# STM32_MPU_IOs.net
KiCad netlist of a schematic drawn in Altium Designer
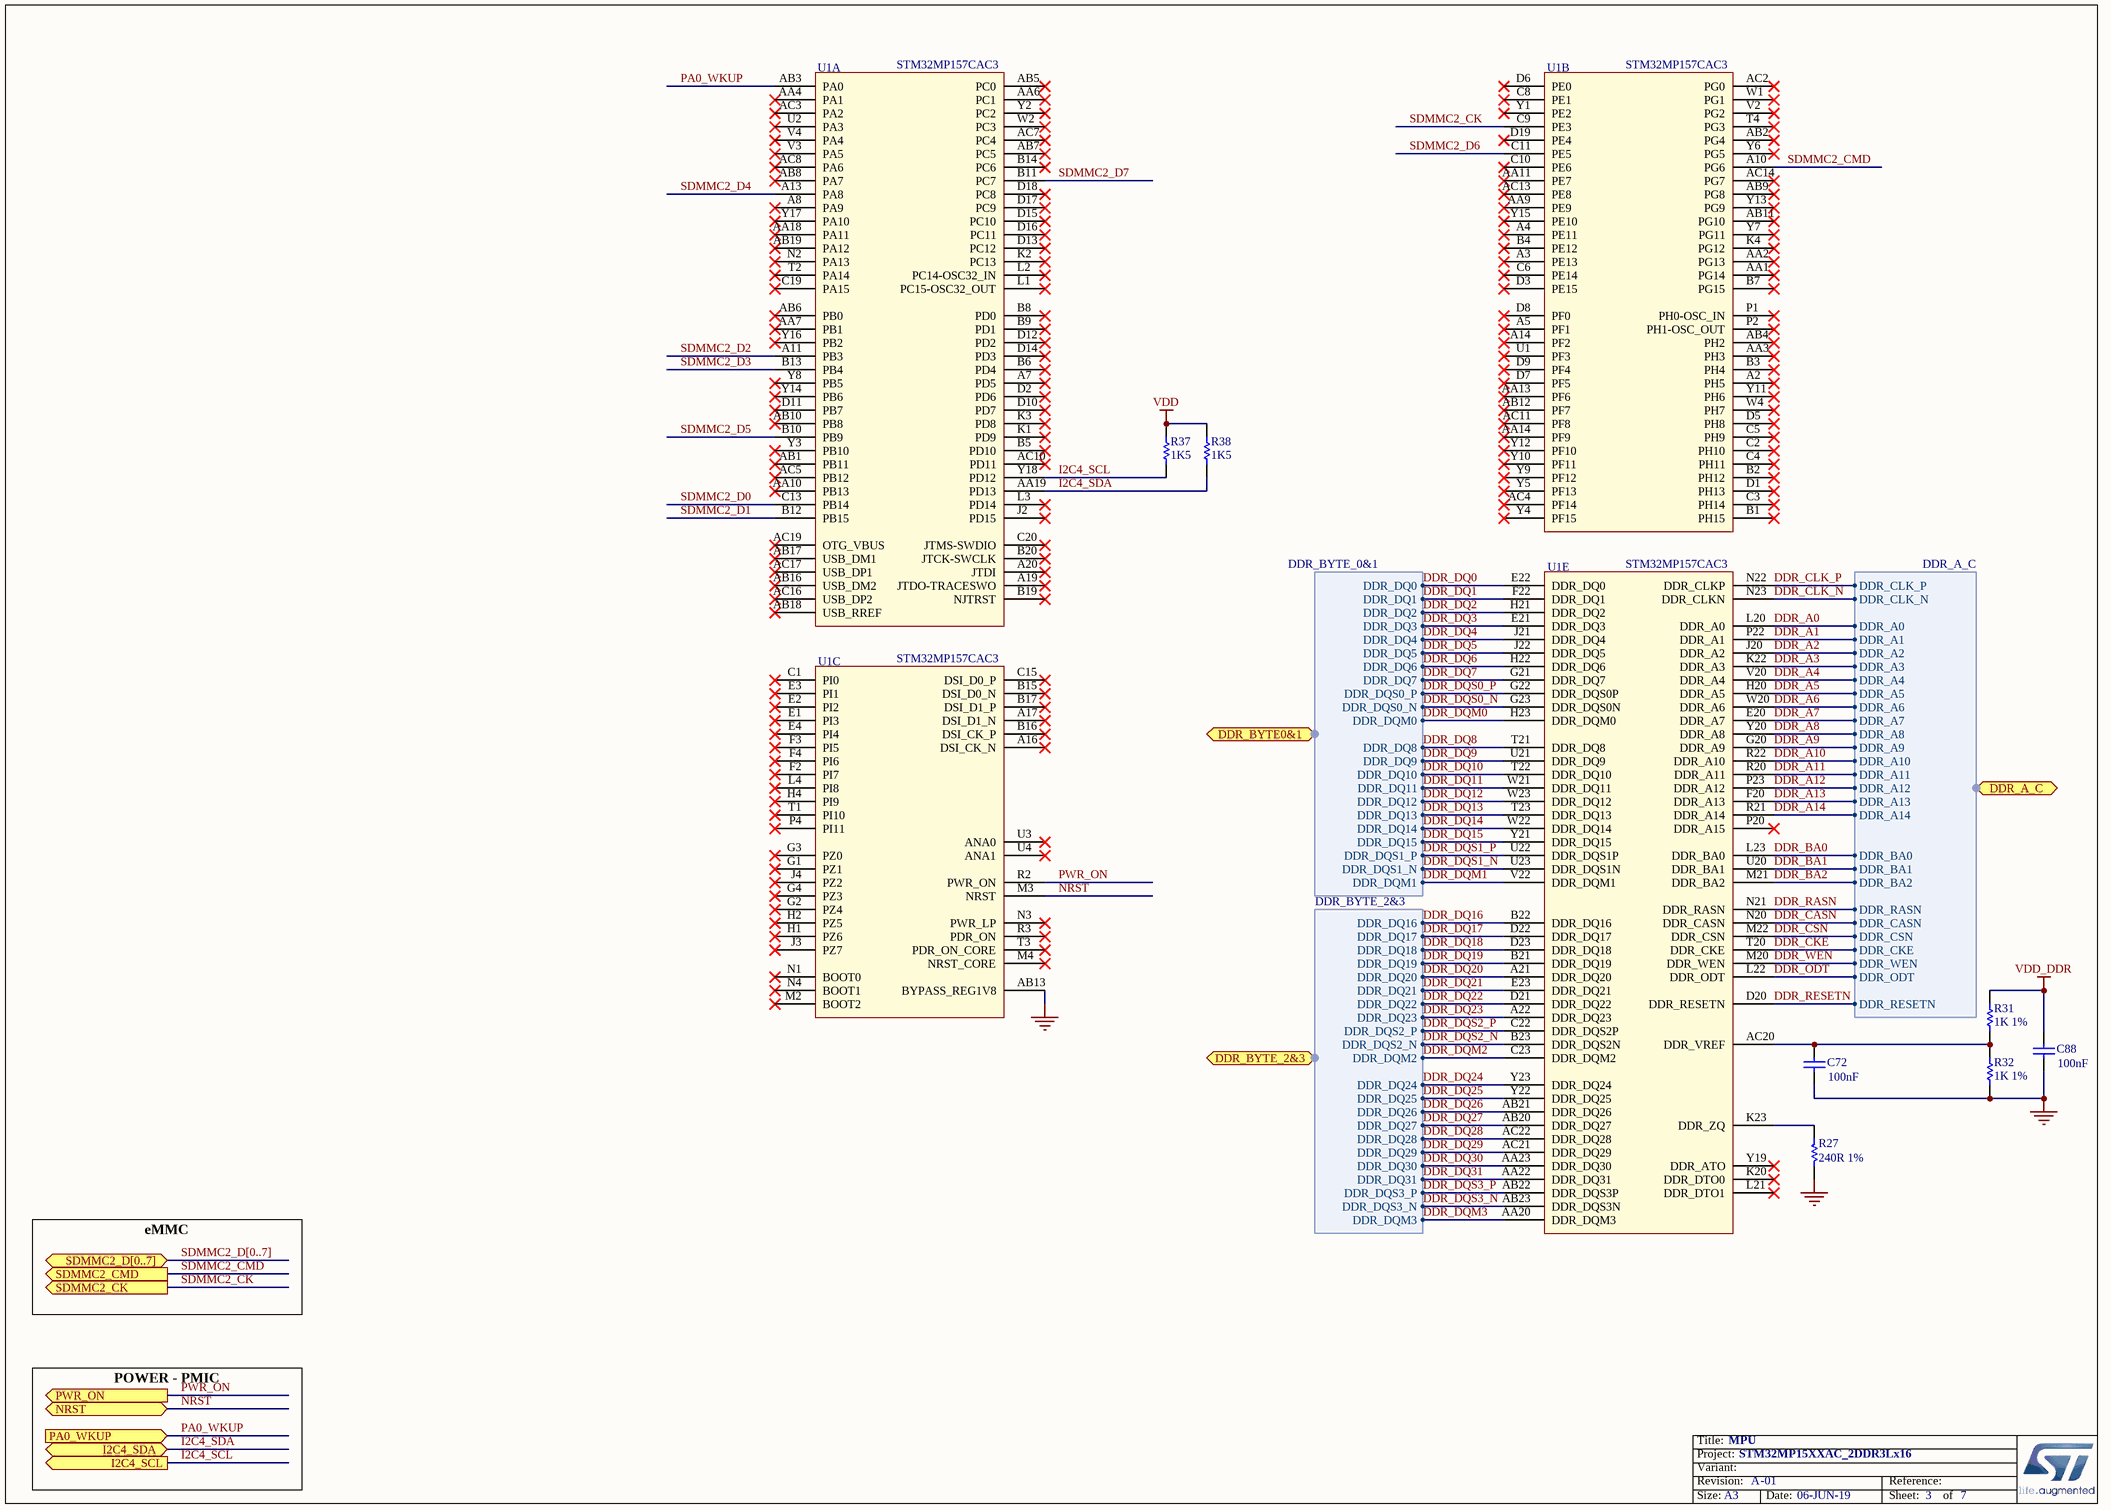
[diagram p0: STM32_MPU_IOs.SchDoc]

(export (version "E")
  (design (tool "Eeschema 10.0.6"))
  (components
    (comp (ref "C72")
      (value "100nF")
      (footprint "C0402")
      (description "Capacitor,100nF,16V,X7R,10%,0402")
      (fields
        (field (name "INTERNAL_PART_NUMBER") "MCD-00006")
        (field (name "MANUFACTURER_PART_NUMBER") "CC0402KRX7R7BB104")
        (field (name "PROVIDED_BY") "Subcon")
      )
      (libsource (lib "MCD_PARTS_database") (part "Capacitor"))
    )
    (comp (ref "C88")
      (value "100nF")
      (footprint "C0402")
      (description "Capacitor,100nF,16V,X7R,10%,0402")
      (fields
        (field (name "INTERNAL_PART_NUMBER") "MCD-00006")
        (field (name "MANUFACTURER_PART_NUMBER") "CC0402KRX7R7BB104")
        (field (name "PROVIDED_BY") "Subcon")
      )
      (libsource (lib "MCD_PARTS_database") (part "Capacitor"))
    )
    (comp (ref "R27")
      (value "240R 1%")
      (footprint "R0402")
      (description "Resistor,240R,0402,1%,1/16W")
      (fields
        (field (name "INTERNAL_PART_NUMBER") "MCD-00120")
        (field (name "MANUFACTURER_PART_NUMBER") "RC0402FR-07240RL")
        (field (name "PROVIDED_BY") "Subcon")
      )
      (libsource (lib "MCD_PARTS_database") (part "Resistor"))
    )
    (comp (ref "R31")
      (value "1K 1%")
      (footprint "R0402")
      (description "Resistor,1K,0402,1%,1/16W")
      (fields
        (field (name "INTERNAL_PART_NUMBER") "MCD-00061")
        (field (name "MANUFACTURER_PART_NUMBER") "RC0402FR-071KL")
        (field (name "PROVIDED_BY") "SUBCO")
      )
      (libsource (lib "MCD_PARTS_database") (part "Resistor"))
    )
    (comp (ref "R32")
      (value "1K 1%")
      (footprint "R0402")
      (description "Resistor,1K,0402,1%,1/16W")
      (fields
        (field (name "INTERNAL_PART_NUMBER") "MCD-00061")
        (field (name "MANUFACTURER_PART_NUMBER") "RC0402FR-071KL")
        (field (name "PROVIDED_BY") "SUBCO")
      )
      (libsource (lib "MCD_PARTS_database") (part "Resistor"))
    )
    (comp (ref "R37")
      (value "1K5")
      (footprint "R0402")
      (description "Resistor,1K5,0402,1%,1/16W")
      (fields
        (field (name "INTERNAL_PART_NUMBER") "MCD-00068")
        (field (name "MANUFACTURER_PART_NUMBER") "RC0402FR-071K5L")
        (field (name "PROVIDED_BY") "Subcon")
      )
      (libsource (lib "MCD_PARTS_database") (part "Resistor"))
    )
    (comp (ref "R38")
      (value "1K5")
      (footprint "R0402")
      (description "Resistor,1K5,0402,1%,1/16W")
      (fields
        (field (name "INTERNAL_PART_NUMBER") "MCD-00068")
        (field (name "MANUFACTURER_PART_NUMBER") "RC0402FR-071K5L")
        (field (name "PROVIDED_BY") "Subcon")
      )
      (libsource (lib "MCD_PARTS_database") (part "Resistor"))
    )
    (comp (ref "U1")
      (value "STM32MP157CAC3")
      (footprint "ICC_TFBGA361_12X12_STM32MP157CAC3_P050-065")
      (description "MPU TFBGA12x12 secure boot+crypto")
      (fields
        (field (name "INTERNAL_PART_NUMBER") "MCD-00677")
        (field (name "MANUFACTURER") "STMICROELECTRONICS")
        (field (name "PROVIDED_BY") "STM")
      )
      (libsource (lib "MCD_PARTS_database") (part "STM32MP157CAC3"))
    )
  )
  (nets
    (net (code "4") (name "/DDR_A0") (class "Default")
      (node (ref "U1") (pin "L20") (pinfunction "DDR_A0_L20") (pintype "passive"))
    )
    (net (code "5") (name "/DDR_A1") (class "Default")
      (node (ref "U1") (pin "P22") (pinfunction "DDR_A1_P22") (pintype "passive"))
    )
    (net (code "6") (name "/DDR_A2") (class "Default")
      (node (ref "U1") (pin "J20") (pinfunction "DDR_A2_J20") (pintype "passive"))
    )
    (net (code "7") (name "/DDR_A3") (class "Default")
      (node (ref "U1") (pin "K22") (pinfunction "DDR_A3_K22") (pintype "passive"))
    )
    (net (code "8") (name "/DDR_A4") (class "Default")
      (node (ref "U1") (pin "V20") (pinfunction "DDR_A4_V20") (pintype "passive"))
    )
    (net (code "9") (name "/DDR_A5") (class "Default")
      (node (ref "U1") (pin "H20") (pinfunction "DDR_A5_H20") (pintype "passive"))
    )
    (net (code "10") (name "/DDR_A6") (class "Default")
      (node (ref "U1") (pin "W20") (pinfunction "DDR_A6_W20") (pintype "passive"))
    )
    (net (code "11") (name "/DDR_A7") (class "Default")
      (node (ref "U1") (pin "E20") (pinfunction "DDR_A7_E20") (pintype "passive"))
    )
    (net (code "12") (name "/DDR_A8") (class "Default")
      (node (ref "U1") (pin "Y20") (pinfunction "DDR_A8_Y20") (pintype "passive"))
    )
    (net (code "13") (name "/DDR_A9") (class "Default")
      (node (ref "U1") (pin "G20") (pinfunction "DDR_A9_G20") (pintype "passive"))
    )
    (net (code "14") (name "/DDR_A10") (class "Default")
      (node (ref "U1") (pin "R22") (pinfunction "DDR_A10_R22") (pintype "passive"))
    )
    (net (code "15") (name "/DDR_A11") (class "Default")
      (node (ref "U1") (pin "R20") (pinfunction "DDR_A11_R20") (pintype "passive"))
    )
    (net (code "16") (name "/DDR_A12") (class "Default")
      (node (ref "U1") (pin "P23") (pinfunction "DDR_A12_P23") (pintype "passive"))
    )
    (net (code "17") (name "/DDR_A13") (class "Default")
      (node (ref "U1") (pin "F20") (pinfunction "DDR_A13_F20") (pintype "passive"))
    )
    (net (code "18") (name "/DDR_A14") (class "Default")
      (node (ref "U1") (pin "R21") (pinfunction "DDR_A14_R21") (pintype "passive"))
    )
    (net (code "19") (name "/DDR_BA0") (class "Default")
      (node (ref "U1") (pin "L23") (pinfunction "DDR_BA0_L23") (pintype "passive"))
    )
    (net (code "20") (name "/DDR_BA1") (class "Default")
      (node (ref "U1") (pin "U20") (pinfunction "DDR_BA1_U20") (pintype "passive"))
    )
    (net (code "21") (name "/DDR_BA2") (class "Default")
      (node (ref "U1") (pin "M21") (pinfunction "DDR_BA2_M21") (pintype "passive"))
    )
    (net (code "22") (name "/DDR_CASN") (class "Default")
      (node (ref "U1") (pin "N20") (pinfunction "DDR_CASN_N20") (pintype "passive"))
    )
    (net (code "23") (name "/DDR_CKE") (class "Default")
      (node (ref "U1") (pin "T20") (pinfunction "DDR_CKE_T20") (pintype "passive"))
    )
    (net (code "24") (name "/DDR_CLK_N") (class "Default")
      (node (ref "U1") (pin "N23") (pinfunction "DDR_CLKN_N23") (pintype "passive"))
    )
    (net (code "25") (name "/DDR_CLK_P") (class "Default")
      (node (ref "U1") (pin "N22") (pinfunction "DDR_CLKP_N22") (pintype "passive"))
    )
    (net (code "26") (name "/DDR_CSN") (class "Default")
      (node (ref "U1") (pin "M22") (pinfunction "DDR_CSN_M22") (pintype "passive"))
    )
    (net (code "27") (name "/DDR_DQ0") (class "Default")
      (node (ref "U1") (pin "E22") (pinfunction "DDR_DQ0_E22") (pintype "passive"))
    )
    (net (code "28") (name "/DDR_DQ1") (class "Default")
      (node (ref "U1") (pin "F22") (pinfunction "DDR_DQ1_F22") (pintype "passive"))
    )
    (net (code "29") (name "/DDR_DQ2") (class "Default")
      (node (ref "U1") (pin "H21") (pinfunction "DDR_DQ2_H21") (pintype "passive"))
    )
    (net (code "30") (name "/DDR_DQ3") (class "Default")
      (node (ref "U1") (pin "E21") (pinfunction "DDR_DQ3_E21") (pintype "passive"))
    )
    (net (code "31") (name "/DDR_DQ4") (class "Default")
      (node (ref "U1") (pin "J21") (pinfunction "DDR_DQ4_J21") (pintype "passive"))
    )
    (net (code "32") (name "/DDR_DQ5") (class "Default")
      (node (ref "U1") (pin "J22") (pinfunction "DDR_DQ5_J22") (pintype "passive"))
    )
    (net (code "33") (name "/DDR_DQ6") (class "Default")
      (node (ref "U1") (pin "H22") (pinfunction "DDR_DQ6_H22") (pintype "passive"))
    )
    (net (code "34") (name "/DDR_DQ7") (class "Default")
      (node (ref "U1") (pin "G21") (pinfunction "DDR_DQ7_G21") (pintype "passive"))
    )
    (net (code "35") (name "/DDR_DQ8") (class "Default")
      (node (ref "U1") (pin "T21") (pinfunction "DDR_DQ8_T21") (pintype "passive"))
    )
    (net (code "36") (name "/DDR_DQ9") (class "Default")
      (node (ref "U1") (pin "U21") (pinfunction "DDR_DQ9_U21") (pintype "passive"))
    )
    (net (code "37") (name "/DDR_DQ10") (class "Default")
      (node (ref "U1") (pin "T22") (pinfunction "DDR_DQ10_T22") (pintype "passive"))
    )
    (net (code "38") (name "/DDR_DQ11") (class "Default")
      (node (ref "U1") (pin "W21") (pinfunction "DDR_DQ11_W21") (pintype "passive"))
    )
    (net (code "39") (name "/DDR_DQ12") (class "Default")
      (node (ref "U1") (pin "W23") (pinfunction "DDR_DQ12_W23") (pintype "passive"))
    )
    (net (code "40") (name "/DDR_DQ13") (class "Default")
      (node (ref "U1") (pin "T23") (pinfunction "DDR_DQ13_T23") (pintype "passive"))
    )
    (net (code "41") (name "/DDR_DQ14") (class "Default")
      (node (ref "U1") (pin "W22") (pinfunction "DDR_DQ14_W22") (pintype "passive"))
    )
    (net (code "42") (name "/DDR_DQ15") (class "Default")
      (node (ref "U1") (pin "Y21") (pinfunction "DDR_DQ15_Y21") (pintype "passive"))
    )
    (net (code "43") (name "/DDR_DQ16") (class "Default")
      (node (ref "U1") (pin "B22") (pinfunction "DDR_DQ16_B22") (pintype "passive"))
    )
    (net (code "44") (name "/DDR_DQ17") (class "Default")
      (node (ref "U1") (pin "D22") (pinfunction "DDR_DQ17_D22") (pintype "passive"))
    )
    (net (code "45") (name "/DDR_DQ18") (class "Default")
      (node (ref "U1") (pin "D23") (pinfunction "DDR_DQ18_D23") (pintype "passive"))
    )
    (net (code "46") (name "/DDR_DQ19") (class "Default")
      (node (ref "U1") (pin "B21") (pinfunction "DDR_DQ19_B21") (pintype "passive"))
    )
    (net (code "47") (name "/DDR_DQ20") (class "Default")
      (node (ref "U1") (pin "A21") (pinfunction "DDR_DQ20_A21") (pintype "passive"))
    )
    (net (code "48") (name "/DDR_DQ21") (class "Default")
      (node (ref "U1") (pin "E23") (pinfunction "DDR_DQ21_E23") (pintype "passive"))
    )
    (net (code "49") (name "/DDR_DQ22") (class "Default")
      (node (ref "U1") (pin "D21") (pinfunction "DDR_DQ22_D21") (pintype "passive"))
    )
    (net (code "50") (name "/DDR_DQ23") (class "Default")
      (node (ref "U1") (pin "A22") (pinfunction "DDR_DQ23_A22") (pintype "passive"))
    )
    (net (code "51") (name "/DDR_DQ24") (class "Default")
      (node (ref "U1") (pin "Y23") (pinfunction "DDR_DQ24_Y23") (pintype "passive"))
    )
    (net (code "52") (name "/DDR_DQ25") (class "Default")
      (node (ref "U1") (pin "Y22") (pinfunction "DDR_DQ25_Y22") (pintype "passive"))
    )
    (net (code "53") (name "/DDR_DQ26") (class "Default")
      (node (ref "U1") (pin "AB21") (pinfunction "DDR_DQ26_AB21") (pintype "passive"))
    )
    (net (code "54") (name "/DDR_DQ27") (class "Default")
      (node (ref "U1") (pin "AB20") (pinfunction "DDR_DQ27_AB20") (pintype "passive"))
    )
    (net (code "55") (name "/DDR_DQ28") (class "Default")
      (node (ref "U1") (pin "AC22") (pinfunction "DDR_DQ28_AC22") (pintype "passive"))
    )
    (net (code "56") (name "/DDR_DQ29") (class "Default")
      (node (ref "U1") (pin "AC21") (pinfunction "DDR_DQ29_AC21") (pintype "passive"))
    )
    (net (code "57") (name "/DDR_DQ30") (class "Default")
      (node (ref "U1") (pin "AA23") (pinfunction "DDR_DQ30_AA23") (pintype "passive"))
    )
    (net (code "58") (name "/DDR_DQ31") (class "Default")
      (node (ref "U1") (pin "AA22") (pinfunction "DDR_DQ31_AA22") (pintype "passive"))
    )
    (net (code "59") (name "/DDR_DQM0") (class "Default")
      (node (ref "U1") (pin "H23") (pinfunction "DDR_DQM0_H23") (pintype "passive"))
    )
    (net (code "60") (name "/DDR_DQM1") (class "Default")
      (node (ref "U1") (pin "V22") (pinfunction "DDR_DQM1_V22") (pintype "passive"))
    )
    (net (code "61") (name "/DDR_DQM2") (class "Default")
      (node (ref "U1") (pin "C23") (pinfunction "DDR_DQM2_C23") (pintype "passive"))
    )
    (net (code "62") (name "/DDR_DQM3") (class "Default")
      (node (ref "U1") (pin "AA20") (pinfunction "DDR_DQM3_AA20") (pintype "passive"))
    )
    (net (code "63") (name "/DDR_DQS0_N") (class "Default")
      (node (ref "U1") (pin "G23") (pinfunction "DDR_DQS0N_G23") (pintype "passive"))
    )
    (net (code "64") (name "/DDR_DQS0_P") (class "Default")
      (node (ref "U1") (pin "G22") (pinfunction "DDR_DQS0P_G22") (pintype "passive"))
    )
    (net (code "65") (name "/DDR_DQS1_N") (class "Default")
      (node (ref "U1") (pin "U23") (pinfunction "DDR_DQS1N_U23") (pintype "passive"))
    )
    (net (code "66") (name "/DDR_DQS1_P") (class "Default")
      (node (ref "U1") (pin "U22") (pinfunction "DDR_DQS1P_U22") (pintype "passive"))
    )
    (net (code "67") (name "/DDR_DQS2_N") (class "Default")
      (node (ref "U1") (pin "B23") (pinfunction "DDR_DQS2N_B23") (pintype "passive"))
    )
    (net (code "68") (name "/DDR_DQS2_P") (class "Default")
      (node (ref "U1") (pin "C22") (pinfunction "DDR_DQS2P_C22") (pintype "passive"))
    )
    (net (code "69") (name "/DDR_DQS3_N") (class "Default")
      (node (ref "U1") (pin "AB23") (pinfunction "DDR_DQS3N_AB23") (pintype "passive"))
    )
    (net (code "70") (name "/DDR_DQS3_P") (class "Default")
      (node (ref "U1") (pin "AB22") (pinfunction "DDR_DQS3P_AB22") (pintype "passive"))
    )
    (net (code "71") (name "/DDR_ODT") (class "Default")
      (node (ref "U1") (pin "L22") (pinfunction "DDR_ODT_L22") (pintype "passive"))
    )
    (net (code "72") (name "/DDR_RASN") (class "Default")
      (node (ref "U1") (pin "N21") (pinfunction "DDR_RASN_N21") (pintype "passive"))
    )
    (net (code "73") (name "/DDR_RESETN") (class "Default")
      (node (ref "U1") (pin "D20") (pinfunction "DDR_RESETN_D20") (pintype "passive"))
    )
    (net (code "74") (name "/DDR_WEN") (class "Default")
      (node (ref "U1") (pin "M20") (pinfunction "DDR_WEN_M20") (pintype "passive"))
    )
    (net (code "75") (name "/I2C4_SCL") (class "Default")
      (node (ref "R37") (pin "2") (pinfunction "2_2") (pintype "passive"))
      (node (ref "U1") (pin "Y18") (pinfunction "PD12_Y18") (pintype "passive"))
    )
    (net (code "76") (name "/I2C4_SDA") (class "Default")
      (node (ref "R38") (pin "2") (pinfunction "2_2") (pintype "passive"))
      (node (ref "U1") (pin "AA19") (pinfunction "PD13_AA19") (pintype "passive"))
    )
    (net (code "77") (name "/NRST") (class "Default")
      (node (ref "U1") (pin "M3") (pinfunction "NRST_M3") (pintype "passive"))
    )
    (net (code "78") (name "/PA0_WKUP") (class "Default")
      (node (ref "U1") (pin "AB3") (pinfunction "PA0_AB3") (pintype "passive"))
    )
    (net (code "79") (name "/PWR_ON") (class "Default")
      (node (ref "U1") (pin "R2") (pinfunction "PWR_ON_R2") (pintype "passive"))
    )
    (net (code "80") (name "/SDMMC2_CK") (class "Default")
      (node (ref "U1") (pin "C9") (pinfunction "PE3_C9") (pintype "passive"))
    )
    (net (code "81") (name "/SDMMC2_CMD") (class "Default")
      (node (ref "U1") (pin "A10") (pinfunction "PG6_A10") (pintype "passive"))
    )
    (net (code "82") (name "/SDMMC2_D0") (class "Default")
      (node (ref "U1") (pin "C13") (pinfunction "PB14_C13") (pintype "passive"))
    )
    (net (code "83") (name "/SDMMC2_D1") (class "Default")
      (node (ref "U1") (pin "B12") (pinfunction "PB15_B12") (pintype "passive"))
    )
    (net (code "84") (name "/SDMMC2_D2") (class "Default")
      (node (ref "U1") (pin "A11") (pinfunction "PB3_A11") (pintype "passive"))
    )
    (net (code "85") (name "/SDMMC2_D3") (class "Default")
      (node (ref "U1") (pin "B13") (pinfunction "PB4_B13") (pintype "passive"))
    )
    (net (code "86") (name "/SDMMC2_D4") (class "Default")
      (node (ref "U1") (pin "A13") (pinfunction "PA8_A13") (pintype "passive"))
    )
    (net (code "87") (name "/SDMMC2_D5") (class "Default")
      (node (ref "U1") (pin "B10") (pinfunction "PB9_B10") (pintype "passive"))
    )
    (net (code "88") (name "/SDMMC2_D6") (class "Default")
      (node (ref "U1") (pin "C11") (pinfunction "PE5_C11") (pintype "passive"))
    )
    (net (code "89") (name "/SDMMC2_D7") (class "Default")
      (node (ref "U1") (pin "B11") (pinfunction "PC7_B11") (pintype "passive"))
    )
    (net (code "94") (name "GND") (class "Default")
      (node (ref "C72") (pin "1") (pinfunction "1_1") (pintype "passive"))
      (node (ref "C88") (pin "1") (pinfunction "1_1") (pintype "passive"))
      (node (ref "R27") (pin "2") (pinfunction "2_2") (pintype "passive"))
      (node (ref "R32") (pin "1") (pinfunction "1_1") (pintype "passive"))
      (node (ref "U1") (pin "AB13") (pinfunction "BYPASS_REG1V8_AB13") (pintype "passive"))
    )
    (net (code "95") (name "Net-(U1E-DDR_VREF)") (class "Default")
      (node (ref "C72") (pin "2") (pinfunction "2_2") (pintype "passive"))
      (node (ref "R31") (pin "1") (pinfunction "1_1") (pintype "passive"))
      (node (ref "R32") (pin "2") (pinfunction "2_2") (pintype "passive"))
      (node (ref "U1") (pin "AC20") (pinfunction "DDR_VREF_AC20") (pintype "passive"))
    )
    (net (code "96") (name "Net-(U1E-DDR_ZQ)") (class "Default")
      (node (ref "R27") (pin "1") (pinfunction "1_1") (pintype "passive"))
      (node (ref "U1") (pin "K23") (pinfunction "DDR_ZQ_K23") (pintype "passive"))
    )
    (net (code "97") (name "VDD") (class "Default")
      (node (ref "R37") (pin "1") (pinfunction "1_1") (pintype "passive"))
      (node (ref "R38") (pin "1") (pinfunction "1_1") (pintype "passive"))
    )
    (net (code "98") (name "VDD_DDR") (class "Default")
      (node (ref "C88") (pin "2") (pinfunction "2_2") (pintype "passive"))
      (node (ref "R31") (pin "2") (pinfunction "2_2") (pintype "passive"))
    )
    (net (code "99") (name "unconnected-(U1A-JTCK-SWCLK-PadB20)") (class "Default")
      (node (ref "U1") (pin "B20") (pinfunction "JTCK-SWCLK_B20") (pintype "passive+no_connect"))
    )
    (net (code "100") (name "unconnected-(U1A-JTDI-PadA20)") (class "Default")
      (node (ref "U1") (pin "A20") (pinfunction "JTDI_A20") (pintype "passive+no_connect"))
    )
    (net (code "101") (name "unconnected-(U1A-JTDO-TRACESWO-PadA19)") (class "Default")
      (node (ref "U1") (pin "A19") (pinfunction "JTDO-TRACESWO_A19") (pintype "passive+no_connect"))
    )
    (net (code "102") (name "unconnected-(U1A-JTMS-SWDIO-PadC20)") (class "Default")
      (node (ref "U1") (pin "C20") (pinfunction "JTMS-SWDIO_C20") (pintype "passive+no_connect"))
    )
    (net (code "103") (name "unconnected-(U1A-NJTRST-PadB19)") (class "Default")
      (node (ref "U1") (pin "B19") (pinfunction "NJTRST_B19") (pintype "passive+no_connect"))
    )
    (net (code "104") (name "unconnected-(U1A-OTG_VBUS-PadAC19)") (class "Default")
      (node (ref "U1") (pin "AC19") (pinfunction "OTG_VBUS_AC19") (pintype "passive+no_connect"))
    )
    (net (code "105") (name "unconnected-(U1A-PA1-PadAA4)") (class "Default")
      (node (ref "U1") (pin "AA4") (pinfunction "PA1_AA4") (pintype "passive+no_connect"))
    )
    (net (code "106") (name "unconnected-(U1A-PA2-PadAC3)") (class "Default")
      (node (ref "U1") (pin "AC3") (pinfunction "PA2_AC3") (pintype "passive+no_connect"))
    )
    (net (code "107") (name "unconnected-(U1A-PA3-PadU2)") (class "Default")
      (node (ref "U1") (pin "U2") (pinfunction "PA3_U2") (pintype "passive+no_connect"))
    )
    (net (code "108") (name "unconnected-(U1A-PA4-PadV4)") (class "Default")
      (node (ref "U1") (pin "V4") (pinfunction "PA4_V4") (pintype "passive+no_connect"))
    )
    (net (code "109") (name "unconnected-(U1A-PA5-PadV3)") (class "Default")
      (node (ref "U1") (pin "V3") (pinfunction "PA5_V3") (pintype "passive+no_connect"))
    )
    (net (code "110") (name "unconnected-(U1A-PA6-PadAC8)") (class "Default")
      (node (ref "U1") (pin "AC8") (pinfunction "PA6_AC8") (pintype "passive+no_connect"))
    )
    (net (code "111") (name "unconnected-(U1A-PA7-PadAB8)") (class "Default")
      (node (ref "U1") (pin "AB8") (pinfunction "PA7_AB8") (pintype "passive+no_connect"))
    )
    (net (code "112") (name "unconnected-(U1A-PA9-PadA8)") (class "Default")
      (node (ref "U1") (pin "A8") (pinfunction "PA9_A8") (pintype "passive+no_connect"))
    )
    (net (code "113") (name "unconnected-(U1A-PA10-PadY17)") (class "Default")
      (node (ref "U1") (pin "Y17") (pinfunction "PA10_Y17") (pintype "passive+no_connect"))
    )
    (net (code "114") (name "unconnected-(U1A-PA11-PadAA18)") (class "Default")
      (node (ref "U1") (pin "AA18") (pinfunction "PA11_AA18") (pintype "passive+no_connect"))
    )
    (net (code "115") (name "unconnected-(U1A-PA12-PadAB19)") (class "Default")
      (node (ref "U1") (pin "AB19") (pinfunction "PA12_AB19") (pintype "passive+no_connect"))
    )
    (net (code "116") (name "unconnected-(U1A-PA13-PadN2)") (class "Default")
      (node (ref "U1") (pin "N2") (pinfunction "PA13_N2") (pintype "passive+no_connect"))
    )
    (net (code "117") (name "unconnected-(U1A-PA14-PadT2)") (class "Default")
      (node (ref "U1") (pin "T2") (pinfunction "PA14_T2") (pintype "passive+no_connect"))
    )
    (net (code "118") (name "unconnected-(U1A-PA15-PadC19)") (class "Default")
      (node (ref "U1") (pin "C19") (pinfunction "PA15_C19") (pintype "passive+no_connect"))
    )
    (net (code "119") (name "unconnected-(U1A-PB0-PadAB6)") (class "Default")
      (node (ref "U1") (pin "AB6") (pinfunction "PB0_AB6") (pintype "passive+no_connect"))
    )
    (net (code "120") (name "unconnected-(U1A-PB1-PadAA7)") (class "Default")
      (node (ref "U1") (pin "AA7") (pinfunction "PB1_AA7") (pintype "passive+no_connect"))
    )
    (net (code "121") (name "unconnected-(U1A-PB2-PadY16)") (class "Default")
      (node (ref "U1") (pin "Y16") (pinfunction "PB2_Y16") (pintype "passive+no_connect"))
    )
    (net (code "122") (name "unconnected-(U1A-PB5-PadY8)") (class "Default")
      (node (ref "U1") (pin "Y8") (pinfunction "PB5_Y8") (pintype "passive+no_connect"))
    )
    (net (code "123") (name "unconnected-(U1A-PB6-PadY14)") (class "Default")
      (node (ref "U1") (pin "Y14") (pinfunction "PB6_Y14") (pintype "passive+no_connect"))
    )
    (net (code "124") (name "unconnected-(U1A-PB7-PadD11)") (class "Default")
      (node (ref "U1") (pin "D11") (pinfunction "PB7_D11") (pintype "passive+no_connect"))
    )
    (net (code "125") (name "unconnected-(U1A-PB8-PadAB10)") (class "Default")
      (node (ref "U1") (pin "AB10") (pinfunction "PB8_AB10") (pintype "passive+no_connect"))
    )
    (net (code "126") (name "unconnected-(U1A-PB10-PadY3)") (class "Default")
      (node (ref "U1") (pin "Y3") (pinfunction "PB10_Y3") (pintype "passive+no_connect"))
    )
    (net (code "127") (name "unconnected-(U1A-PB11-PadAB1)") (class "Default")
      (node (ref "U1") (pin "AB1") (pinfunction "PB11_AB1") (pintype "passive+no_connect"))
    )
    (net (code "128") (name "unconnected-(U1A-PB12-PadAC5)") (class "Default")
      (node (ref "U1") (pin "AC5") (pinfunction "PB12_AC5") (pintype "passive+no_connect"))
    )
    (net (code "129") (name "unconnected-(U1A-PB13-PadAA10)") (class "Default")
      (node (ref "U1") (pin "AA10") (pinfunction "PB13_AA10") (pintype "passive+no_connect"))
    )
    (net (code "130") (name "unconnected-(U1A-PC0-PadAB5)") (class "Default")
      (node (ref "U1") (pin "AB5") (pinfunction "PC0_AB5") (pintype "passive+no_connect"))
    )
    (net (code "131") (name "unconnected-(U1A-PC1-PadAA6)") (class "Default")
      (node (ref "U1") (pin "AA6") (pinfunction "PC1_AA6") (pintype "passive+no_connect"))
    )
    (net (code "132") (name "unconnected-(U1A-PC2-PadY2)") (class "Default")
      (node (ref "U1") (pin "Y2") (pinfunction "PC2_Y2") (pintype "passive+no_connect"))
    )
    (net (code "133") (name "unconnected-(U1A-PC3-PadW2)") (class "Default")
      (node (ref "U1") (pin "W2") (pinfunction "PC3_W2") (pintype "passive+no_connect"))
    )
    (net (code "134") (name "unconnected-(U1A-PC4-PadAC7)") (class "Default")
      (node (ref "U1") (pin "AC7") (pinfunction "PC4_AC7") (pintype "passive+no_connect"))
    )
    (net (code "135") (name "unconnected-(U1A-PC5-PadAB7)") (class "Default")
      (node (ref "U1") (pin "AB7") (pinfunction "PC5_AB7") (pintype "passive+no_connect"))
    )
    (net (code "136") (name "unconnected-(U1A-PC6-PadB14)") (class "Default")
      (node (ref "U1") (pin "B14") (pinfunction "PC6_B14") (pintype "passive+no_connect"))
    )
    (net (code "137") (name "unconnected-(U1A-PC8-PadD18)") (class "Default")
      (node (ref "U1") (pin "D18") (pinfunction "PC8_D18") (pintype "passive+no_connect"))
    )
    (net (code "138") (name "unconnected-(U1A-PC9-PadD17)") (class "Default")
      (node (ref "U1") (pin "D17") (pinfunction "PC9_D17") (pintype "passive+no_connect"))
    )
    (net (code "139") (name "unconnected-(U1A-PC10-PadD15)") (class "Default")
      (node (ref "U1") (pin "D15") (pinfunction "PC10_D15") (pintype "passive+no_connect"))
    )
    (net (code "140") (name "unconnected-(U1A-PC11-PadD16)") (class "Default")
      (node (ref "U1") (pin "D16") (pinfunction "PC11_D16") (pintype "passive+no_connect"))
    )
    (net (code "141") (name "unconnected-(U1A-PC12-PadD13)") (class "Default")
      (node (ref "U1") (pin "D13") (pinfunction "PC12_D13") (pintype "passive+no_connect"))
    )
    (net (code "142") (name "unconnected-(U1A-PC13-PadK2)") (class "Default")
      (node (ref "U1") (pin "K2") (pinfunction "PC13_K2") (pintype "passive+no_connect"))
    )
    (net (code "143") (name "unconnected-(U1A-PC14-OSC32_IN-PadL2)") (class "Default")
      (node (ref "U1") (pin "L2") (pinfunction "PC14-OSC32_IN_L2") (pintype "passive+no_connect"))
    )
    (net (code "144") (name "unconnected-(U1A-PC15-OSC32_OUT-PadL1)") (class "Default")
      (node (ref "U1") (pin "L1") (pinfunction "PC15-OSC32_OUT_L1") (pintype "passive+no_connect"))
    )
    (net (code "145") (name "unconnected-(U1A-PD0-PadB8)") (class "Default")
      (node (ref "U1") (pin "B8") (pinfunction "PD0_B8") (pintype "passive+no_connect"))
    )
    (net (code "146") (name "unconnected-(U1A-PD1-PadB9)") (class "Default")
      (node (ref "U1") (pin "B9") (pinfunction "PD1_B9") (pintype "passive+no_connect"))
    )
    (net (code "147") (name "unconnected-(U1A-PD2-PadD12)") (class "Default")
      (node (ref "U1") (pin "D12") (pinfunction "PD2_D12") (pintype "passive+no_connect"))
    )
    (net (code "148") (name "unconnected-(U1A-PD3-PadD14)") (class "Default")
      (node (ref "U1") (pin "D14") (pinfunction "PD3_D14") (pintype "passive+no_connect"))
    )
    (net (code "149") (name "unconnected-(U1A-PD4-PadB6)") (class "Default")
      (node (ref "U1") (pin "B6") (pinfunction "PD4_B6") (pintype "passive+no_connect"))
    )
    (net (code "150") (name "unconnected-(U1A-PD5-PadA7)") (class "Default")
      (node (ref "U1") (pin "A7") (pinfunction "PD5_A7") (pintype "passive+no_connect"))
    )
    (net (code "151") (name "unconnected-(U1A-PD6-PadD2)") (class "Default")
      (node (ref "U1") (pin "D2") (pinfunction "PD6_D2") (pintype "passive+no_connect"))
    )
    (net (code "152") (name "unconnected-(U1A-PD7-PadD10)") (class "Default")
      (node (ref "U1") (pin "D10") (pinfunction "PD7_D10") (pintype "passive+no_connect"))
    )
    (net (code "153") (name "unconnected-(U1A-PD8-PadK3)") (class "Default")
      (node (ref "U1") (pin "K3") (pinfunction "PD8_K3") (pintype "passive+no_connect"))
    )
    (net (code "154") (name "unconnected-(U1A-PD9-PadK1)") (class "Default")
      (node (ref "U1") (pin "K1") (pinfunction "PD9_K1") (pintype "passive+no_connect"))
    )
    (net (code "155") (name "unconnected-(U1A-PD10-PadB5)") (class "Default")
      (node (ref "U1") (pin "B5") (pinfunction "PD10_B5") (pintype "passive+no_connect"))
    )
    (net (code "156") (name "unconnected-(U1A-PD11-PadAC10)") (class "Default")
      (node (ref "U1") (pin "AC10") (pinfunction "PD11_AC10") (pintype "passive+no_connect"))
    )
    (net (code "157") (name "unconnected-(U1A-PD14-PadL3)") (class "Default")
      (node (ref "U1") (pin "L3") (pinfunction "PD14_L3") (pintype "passive+no_connect"))
    )
    (net (code "158") (name "unconnected-(U1A-PD15-PadJ2)") (class "Default")
      (node (ref "U1") (pin "J2") (pinfunction "PD15_J2") (pintype "passive+no_connect"))
    )
    (net (code "159") (name "unconnected-(U1A-USB_DM1-PadAB17)") (class "Default")
      (node (ref "U1") (pin "AB17") (pinfunction "USB_DM1_AB17") (pintype "passive+no_connect"))
    )
    (net (code "160") (name "unconnected-(U1A-USB_DM2-PadAB16)") (class "Default")
      (node (ref "U1") (pin "AB16") (pinfunction "USB_DM2_AB16") (pintype "passive+no_connect"))
    )
    (net (code "161") (name "unconnected-(U1A-USB_DP1-PadAC17)") (class "Default")
      (node (ref "U1") (pin "AC17") (pinfunction "USB_DP1_AC17") (pintype "passive+no_connect"))
    )
    (net (code "162") (name "unconnected-(U1A-USB_DP2-PadAC16)") (class "Default")
      (node (ref "U1") (pin "AC16") (pinfunction "USB_DP2_AC16") (pintype "passive+no_connect"))
    )
    (net (code "163") (name "unconnected-(U1A-USB_RREF-PadAB18)") (class "Default")
      (node (ref "U1") (pin "AB18") (pinfunction "USB_RREF_AB18") (pintype "passive+no_connect"))
    )
    (net (code "164") (name "unconnected-(U1B-PE0-PadD6)") (class "Default")
      (node (ref "U1") (pin "D6") (pinfunction "PE0_D6") (pintype "passive+no_connect"))
    )
    (net (code "165") (name "unconnected-(U1B-PE1-PadC8)") (class "Default")
      (node (ref "U1") (pin "C8") (pinfunction "PE1_C8") (pintype "passive+no_connect"))
    )
    (net (code "166") (name "unconnected-(U1B-PE2-PadY1)") (class "Default")
      (node (ref "U1") (pin "Y1") (pinfunction "PE2_Y1") (pintype "passive+no_connect"))
    )
    (net (code "167") (name "unconnected-(U1B-PE4-PadD19)") (class "Default")
      (node (ref "U1") (pin "D19") (pinfunction "PE4_D19") (pintype "passive+no_connect"))
    )
    (net (code "168") (name "unconnected-(U1B-PE6-PadC10)") (class "Default")
      (node (ref "U1") (pin "C10") (pinfunction "PE6_C10") (pintype "passive+no_connect"))
    )
    (net (code "169") (name "unconnected-(U1B-PE7-PadAA11)") (class "Default")
      (node (ref "U1") (pin "AA11") (pinfunction "PE7_AA11") (pintype "passive+no_connect"))
    )
    (net (code "170") (name "unconnected-(U1B-PE8-PadAC13)") (class "Default")
      (node (ref "U1") (pin "AC13") (pinfunction "PE8_AC13") (pintype "passive+no_connect"))
    )
    (net (code "171") (name "unconnected-(U1B-PE9-PadAA9)") (class "Default")
      (node (ref "U1") (pin "AA9") (pinfunction "PE9_AA9") (pintype "passive+no_connect"))
    )
    (net (code "172") (name "unconnected-(U1B-PE10-PadY15)") (class "Default")
      (node (ref "U1") (pin "Y15") (pinfunction "PE10_Y15") (pintype "passive+no_connect"))
    )
    (net (code "173") (name "unconnected-(U1B-PE11-PadA4)") (class "Default")
      (node (ref "U1") (pin "A4") (pinfunction "PE11_A4") (pintype "passive+no_connect"))
    )
    (net (code "174") (name "unconnected-(U1B-PE12-PadB4)") (class "Default")
      (node (ref "U1") (pin "B4") (pinfunction "PE12_B4") (pintype "passive+no_connect"))
    )
    (net (code "175") (name "unconnected-(U1B-PE13-PadA3)") (class "Default")
      (node (ref "U1") (pin "A3") (pinfunction "PE13_A3") (pintype "passive+no_connect"))
    )
    (net (code "176") (name "unconnected-(U1B-PE14-PadC6)") (class "Default")
      (node (ref "U1") (pin "C6") (pinfunction "PE14_C6") (pintype "passive+no_connect"))
    )
    (net (code "177") (name "unconnected-(U1B-PE15-PadD3)") (class "Default")
      (node (ref "U1") (pin "D3") (pinfunction "PE15_D3") (pintype "passive+no_connect"))
    )
    (net (code "178") (name "unconnected-(U1B-PF0-PadD8)") (class "Default")
      (node (ref "U1") (pin "D8") (pinfunction "PF0_D8") (pintype "passive+no_connect"))
    )
    (net (code "179") (name "unconnected-(U1B-PF1-PadA5)") (class "Default")
      (node (ref "U1") (pin "A5") (pinfunction "PF1_A5") (pintype "passive+no_connect"))
    )
    (net (code "180") (name "unconnected-(U1B-PF2-PadA14)") (class "Default")
      (node (ref "U1") (pin "A14") (pinfunction "PF2_A14") (pintype "passive+no_connect"))
    )
    (net (code "181") (name "unconnected-(U1B-PF3-PadU1)") (class "Default")
      (node (ref "U1") (pin "U1") (pinfunction "PF3_U1") (pintype "passive+no_connect"))
    )
    (net (code "182") (name "unconnected-(U1B-PF4-PadD9)") (class "Default")
      (node (ref "U1") (pin "D9") (pinfunction "PF4_D9") (pintype "passive+no_connect"))
    )
    (net (code "183") (name "unconnected-(U1B-PF5-PadD7)") (class "Default")
      (node (ref "U1") (pin "D7") (pinfunction "PF5_D7") (pintype "passive+no_connect"))
    )
    (net (code "184") (name "unconnected-(U1B-PF6-PadAA13)") (class "Default")
      (node (ref "U1") (pin "AA13") (pinfunction "PF6_AA13") (pintype "passive+no_connect"))
    )
    (net (code "185") (name "unconnected-(U1B-PF7-PadAB12)") (class "Default")
      (node (ref "U1") (pin "AB12") (pinfunction "PF7_AB12") (pintype "passive+no_connect"))
    )
    (net (code "186") (name "unconnected-(U1B-PF8-PadAC11)") (class "Default")
      (node (ref "U1") (pin "AC11") (pinfunction "PF8_AC11") (pintype "passive+no_connect"))
    )
    (net (code "187") (name "unconnected-(U1B-PF9-PadAA14)") (class "Default")
      (node (ref "U1") (pin "AA14") (pinfunction "PF9_AA14") (pintype "passive+no_connect"))
    )
    (net (code "188") (name "unconnected-(U1B-PF10-PadY12)") (class "Default")
      (node (ref "U1") (pin "Y12") (pinfunction "PF10_Y12") (pintype "passive+no_connect"))
    )
    (net (code "189") (name "unconnected-(U1B-PF11-PadY10)") (class "Default")
      (node (ref "U1") (pin "Y10") (pinfunction "PF11_Y10") (pintype "passive+no_connect"))
    )
    (net (code "190") (name "unconnected-(U1B-PF12-PadY9)") (class "Default")
      (node (ref "U1") (pin "Y9") (pinfunction "PF12_Y9") (pintype "passive+no_connect"))
    )
    (net (code "191") (name "unconnected-(U1B-PF13-PadY5)") (class "Default")
      (node (ref "U1") (pin "Y5") (pinfunction "PF13_Y5") (pintype "passive+no_connect"))
    )
    (net (code "192") (name "unconnected-(U1B-PF14-PadAC4)") (class "Default")
      (node (ref "U1") (pin "AC4") (pinfunction "PF14_AC4") (pintype "passive+no_connect"))
    )
    (net (code "193") (name "unconnected-(U1B-PF15-PadY4)") (class "Default")
      (node (ref "U1") (pin "Y4") (pinfunction "PF15_Y4") (pintype "passive+no_connect"))
    )
    (net (code "194") (name "unconnected-(U1B-PG0-PadAC2)") (class "Default")
      (node (ref "U1") (pin "AC2") (pinfunction "PG0_AC2") (pintype "passive+no_connect"))
    )
    (net (code "195") (name "unconnected-(U1B-PG1-PadW1)") (class "Default")
      (node (ref "U1") (pin "W1") (pinfunction "PG1_W1") (pintype "passive+no_connect"))
    )
    (net (code "196") (name "unconnected-(U1B-PG2-PadV2)") (class "Default")
      (node (ref "U1") (pin "V2") (pinfunction "PG2_V2") (pintype "passive+no_connect"))
    )
    (net (code "197") (name "unconnected-(U1B-PG3-PadT4)") (class "Default")
      (node (ref "U1") (pin "T4") (pinfunction "PG3_T4") (pintype "passive+no_connect"))
    )
    (net (code "198") (name "unconnected-(U1B-PG4-PadAB2)") (class "Default")
      (node (ref "U1") (pin "AB2") (pinfunction "PG4_AB2") (pintype "passive+no_connect"))
    )
    (net (code "199") (name "unconnected-(U1B-PG5-PadY6)") (class "Default")
      (node (ref "U1") (pin "Y6") (pinfunction "PG5_Y6") (pintype "passive+no_connect"))
    )
    (net (code "200") (name "unconnected-(U1B-PG7-PadAC14)") (class "Default")
      (node (ref "U1") (pin "AC14") (pinfunction "PG7_AC14") (pintype "passive+no_connect"))
    )
    (net (code "201") (name "unconnected-(U1B-PG8-PadAB9)") (class "Default")
      (node (ref "U1") (pin "AB9") (pinfunction "PG8_AB9") (pintype "passive+no_connect"))
    )
    (net (code "202") (name "unconnected-(U1B-PG9-PadY13)") (class "Default")
      (node (ref "U1") (pin "Y13") (pinfunction "PG9_Y13") (pintype "passive+no_connect"))
    )
    (net (code "203") (name "unconnected-(U1B-PG10-PadAB11)") (class "Default")
      (node (ref "U1") (pin "AB11") (pinfunction "PG10_AB11") (pintype "passive+no_connect"))
    )
    (net (code "204") (name "unconnected-(U1B-PG11-PadY7)") (class "Default")
      (node (ref "U1") (pin "Y7") (pinfunction "PG11_Y7") (pintype "passive+no_connect"))
    )
    (net (code "205") (name "unconnected-(U1B-PG12-PadK4)") (class "Default")
      (node (ref "U1") (pin "K4") (pinfunction "PG12_K4") (pintype "passive+no_connect"))
    )
    (net (code "206") (name "unconnected-(U1B-PG13-PadAA2)") (class "Default")
      (node (ref "U1") (pin "AA2") (pinfunction "PG13_AA2") (pintype "passive+no_connect"))
    )
    (net (code "207") (name "unconnected-(U1B-PG14-PadAA1)") (class "Default")
      (node (ref "U1") (pin "AA1") (pinfunction "PG14_AA1") (pintype "passive+no_connect"))
    )
    (net (code "208") (name "unconnected-(U1B-PG15-PadB7)") (class "Default")
      (node (ref "U1") (pin "B7") (pinfunction "PG15_B7") (pintype "passive+no_connect"))
    )
    (net (code "209") (name "unconnected-(U1B-PH0-OSC_IN-PadP1)") (class "Default")
      (node (ref "U1") (pin "P1") (pinfunction "PH0-OSC_IN_P1") (pintype "passive+no_connect"))
    )
    (net (code "210") (name "unconnected-(U1B-PH1-OSC_OUT-PadP2)") (class "Default")
      (node (ref "U1") (pin "P2") (pinfunction "PH1-OSC_OUT_P2") (pintype "passive+no_connect"))
    )
    (net (code "211") (name "unconnected-(U1B-PH2-PadAB4)") (class "Default")
      (node (ref "U1") (pin "AB4") (pinfunction "PH2_AB4") (pintype "passive+no_connect"))
    )
    (net (code "212") (name "unconnected-(U1B-PH3-PadAA3)") (class "Default")
      (node (ref "U1") (pin "AA3") (pinfunction "PH3_AA3") (pintype "passive+no_connect"))
    )
    (net (code "213") (name "unconnected-(U1B-PH4-PadB3)") (class "Default")
      (node (ref "U1") (pin "B3") (pinfunction "PH4_B3") (pintype "passive+no_connect"))
    )
    (net (code "214") (name "unconnected-(U1B-PH5-PadA2)") (class "Default")
      (node (ref "U1") (pin "A2") (pinfunction "PH5_A2") (pintype "passive+no_connect"))
    )
    (net (code "215") (name "unconnected-(U1B-PH6-PadY11)") (class "Default")
      (node (ref "U1") (pin "Y11") (pinfunction "PH6_Y11") (pintype "passive+no_connect"))
    )
    (net (code "216") (name "unconnected-(U1B-PH7-PadW4)") (class "Default")
      (node (ref "U1") (pin "W4") (pinfunction "PH7_W4") (pintype "passive+no_connect"))
    )
    (net (code "217") (name "unconnected-(U1B-PH8-PadD5)") (class "Default")
      (node (ref "U1") (pin "D5") (pinfunction "PH8_D5") (pintype "passive+no_connect"))
    )
    (net (code "218") (name "unconnected-(U1B-PH9-PadC5)") (class "Default")
      (node (ref "U1") (pin "C5") (pinfunction "PH9_C5") (pintype "passive+no_connect"))
    )
    (net (code "219") (name "unconnected-(U1B-PH10-PadC2)") (class "Default")
      (node (ref "U1") (pin "C2") (pinfunction "PH10_C2") (pintype "passive+no_connect"))
    )
    (net (code "220") (name "unconnected-(U1B-PH11-PadC4)") (class "Default")
      (node (ref "U1") (pin "C4") (pinfunction "PH11_C4") (pintype "passive+no_connect"))
    )
    (net (code "221") (name "unconnected-(U1B-PH12-PadB2)") (class "Default")
      (node (ref "U1") (pin "B2") (pinfunction "PH12_B2") (pintype "passive+no_connect"))
    )
    (net (code "222") (name "unconnected-(U1B-PH13-PadD1)") (class "Default")
      (node (ref "U1") (pin "D1") (pinfunction "PH13_D1") (pintype "passive+no_connect"))
    )
    (net (code "223") (name "unconnected-(U1B-PH14-PadC3)") (class "Default")
      (node (ref "U1") (pin "C3") (pinfunction "PH14_C3") (pintype "passive+no_connect"))
    )
    (net (code "224") (name "unconnected-(U1B-PH15-PadB1)") (class "Default")
      (node (ref "U1") (pin "B1") (pinfunction "PH15_B1") (pintype "passive+no_connect"))
    )
    (net (code "225") (name "unconnected-(U1C-ANA0-PadU3)") (class "Default")
      (node (ref "U1") (pin "U3") (pinfunction "ANA0_U3") (pintype "passive+no_connect"))
    )
    (net (code "226") (name "unconnected-(U1C-ANA1-PadU4)") (class "Default")
      (node (ref "U1") (pin "U4") (pinfunction "ANA1_U4") (pintype "passive+no_connect"))
    )
    (net (code "227") (name "unconnected-(U1C-BOOT0-PadN1)") (class "Default")
      (node (ref "U1") (pin "N1") (pinfunction "BOOT0_N1") (pintype "passive+no_connect"))
    )
    (net (code "228") (name "unconnected-(U1C-BOOT1-PadN4)") (class "Default")
      (node (ref "U1") (pin "N4") (pinfunction "BOOT1_N4") (pintype "passive+no_connect"))
    )
    (net (code "229") (name "unconnected-(U1C-BOOT2-PadM2)") (class "Default")
      (node (ref "U1") (pin "M2") (pinfunction "BOOT2_M2") (pintype "passive+no_connect"))
    )
    (net (code "230") (name "unconnected-(U1C-DSI_CK_N-PadA16)") (class "Default")
      (node (ref "U1") (pin "A16") (pinfunction "DSI_CK_N_A16") (pintype "passive+no_connect"))
    )
    (net (code "231") (name "unconnected-(U1C-DSI_CK_P-PadB16)") (class "Default")
      (node (ref "U1") (pin "B16") (pinfunction "DSI_CK_P_B16") (pintype "passive+no_connect"))
    )
    (net (code "232") (name "unconnected-(U1C-DSI_D0_N-PadB15)") (class "Default")
      (node (ref "U1") (pin "B15") (pinfunction "DSI_D0_N_B15") (pintype "passive+no_connect"))
    )
    (net (code "233") (name "unconnected-(U1C-DSI_D0_P-PadC15)") (class "Default")
      (node (ref "U1") (pin "C15") (pinfunction "DSI_D0_P_C15") (pintype "passive+no_connect"))
    )
    (net (code "234") (name "unconnected-(U1C-DSI_D1_N-PadA17)") (class "Default")
      (node (ref "U1") (pin "A17") (pinfunction "DSI_D1_N_A17") (pintype "passive+no_connect"))
    )
    (net (code "235") (name "unconnected-(U1C-DSI_D1_P-PadB17)") (class "Default")
      (node (ref "U1") (pin "B17") (pinfunction "DSI_D1_P_B17") (pintype "passive+no_connect"))
    )
    (net (code "236") (name "unconnected-(U1C-NRST_CORE-PadM4)") (class "Default")
      (node (ref "U1") (pin "M4") (pinfunction "NRST_CORE_M4") (pintype "passive+no_connect"))
    )
    (net (code "237") (name "unconnected-(U1C-PDR_ON-PadR3)") (class "Default")
      (node (ref "U1") (pin "R3") (pinfunction "PDR_ON_R3") (pintype "passive+no_connect"))
    )
    (net (code "238") (name "unconnected-(U1C-PDR_ON_CORE-PadT3)") (class "Default")
      (node (ref "U1") (pin "T3") (pinfunction "PDR_ON_CORE_T3") (pintype "passive+no_connect"))
    )
    (net (code "239") (name "unconnected-(U1C-PI0-PadC1)") (class "Default")
      (node (ref "U1") (pin "C1") (pinfunction "PI0_C1") (pintype "passive+no_connect"))
    )
    (net (code "240") (name "unconnected-(U1C-PI1-PadE3)") (class "Default")
      (node (ref "U1") (pin "E3") (pinfunction "PI1_E3") (pintype "passive+no_connect"))
    )
    (net (code "241") (name "unconnected-(U1C-PI2-PadE2)") (class "Default")
      (node (ref "U1") (pin "E2") (pinfunction "PI2_E2") (pintype "passive+no_connect"))
    )
    (net (code "242") (name "unconnected-(U1C-PI3-PadE1)") (class "Default")
      (node (ref "U1") (pin "E1") (pinfunction "PI3_E1") (pintype "passive+no_connect"))
    )
    (net (code "243") (name "unconnected-(U1C-PI4-PadE4)") (class "Default")
      (node (ref "U1") (pin "E4") (pinfunction "PI4_E4") (pintype "passive+no_connect"))
    )
    (net (code "244") (name "unconnected-(U1C-PI5-PadF3)") (class "Default")
      (node (ref "U1") (pin "F3") (pinfunction "PI5_F3") (pintype "passive+no_connect"))
    )
    (net (code "245") (name "unconnected-(U1C-PI6-PadF4)") (class "Default")
      (node (ref "U1") (pin "F4") (pinfunction "PI6_F4") (pintype "passive+no_connect"))
    )
    (net (code "246") (name "unconnected-(U1C-PI7-PadF2)") (class "Default")
      (node (ref "U1") (pin "F2") (pinfunction "PI7_F2") (pintype "passive+no_connect"))
    )
    (net (code "247") (name "unconnected-(U1C-PI8-PadL4)") (class "Default")
      (node (ref "U1") (pin "L4") (pinfunction "PI8_L4") (pintype "passive+no_connect"))
    )
    (net (code "248") (name "unconnected-(U1C-PI9-PadH4)") (class "Default")
      (node (ref "U1") (pin "H4") (pinfunction "PI9_H4") (pintype "passive+no_connect"))
    )
    (net (code "249") (name "unconnected-(U1C-PI10-PadT1)") (class "Default")
      (node (ref "U1") (pin "T1") (pinfunction "PI10_T1") (pintype "passive+no_connect"))
    )
    (net (code "250") (name "unconnected-(U1C-PI11-PadP4)") (class "Default")
      (node (ref "U1") (pin "P4") (pinfunction "PI11_P4") (pintype "passive+no_connect"))
    )
    (net (code "251") (name "unconnected-(U1C-PWR_LP-PadN3)") (class "Default")
      (node (ref "U1") (pin "N3") (pinfunction "PWR_LP_N3") (pintype "passive+no_connect"))
    )
    (net (code "252") (name "unconnected-(U1C-PZ0-PadG3)") (class "Default")
      (node (ref "U1") (pin "G3") (pinfunction "PZ0_G3") (pintype "passive+no_connect"))
    )
    (net (code "253") (name "unconnected-(U1C-PZ1-PadG1)") (class "Default")
      (node (ref "U1") (pin "G1") (pinfunction "PZ1_G1") (pintype "passive+no_connect"))
    )
    (net (code "254") (name "unconnected-(U1C-PZ2-PadJ4)") (class "Default")
      (node (ref "U1") (pin "J4") (pinfunction "PZ2_J4") (pintype "passive+no_connect"))
    )
    (net (code "255") (name "unconnected-(U1C-PZ3-PadG4)") (class "Default")
      (node (ref "U1") (pin "G4") (pinfunction "PZ3_G4") (pintype "passive+no_connect"))
    )
    (net (code "256") (name "unconnected-(U1C-PZ4-PadG2)") (class "Default")
      (node (ref "U1") (pin "G2") (pinfunction "PZ4_G2") (pintype "passive+no_connect"))
    )
    (net (code "257") (name "unconnected-(U1C-PZ5-PadH2)") (class "Default")
      (node (ref "U1") (pin "H2") (pinfunction "PZ5_H2") (pintype "passive+no_connect"))
    )
    (net (code "258") (name "unconnected-(U1C-PZ6-PadH1)") (class "Default")
      (node (ref "U1") (pin "H1") (pinfunction "PZ6_H1") (pintype "passive+no_connect"))
    )
    (net (code "259") (name "unconnected-(U1C-PZ7-PadJ3)") (class "Default")
      (node (ref "U1") (pin "J3") (pinfunction "PZ7_J3") (pintype "passive+no_connect"))
    )
    (net (code "260") (name "unconnected-(U1E-DDR_A15-PadP20)") (class "Default")
      (node (ref "U1") (pin "P20") (pinfunction "DDR_A15_P20") (pintype "passive+no_connect"))
    )
    (net (code "261") (name "unconnected-(U1E-DDR_ATO-PadY19)") (class "Default")
      (node (ref "U1") (pin "Y19") (pinfunction "DDR_ATO_Y19") (pintype "passive+no_connect"))
    )
    (net (code "262") (name "unconnected-(U1E-DDR_DTO0-PadK20)") (class "Default")
      (node (ref "U1") (pin "K20") (pinfunction "DDR_DTO0_K20") (pintype "passive+no_connect"))
    )
    (net (code "263") (name "unconnected-(U1E-DDR_DTO1-PadL21)") (class "Default")
      (node (ref "U1") (pin "L21") (pinfunction "DDR_DTO1_L21") (pintype "passive+no_connect"))
    )
  )
)
